# mega_pin_out.net
KiCad netlist of a schematic drawn in EAGLE
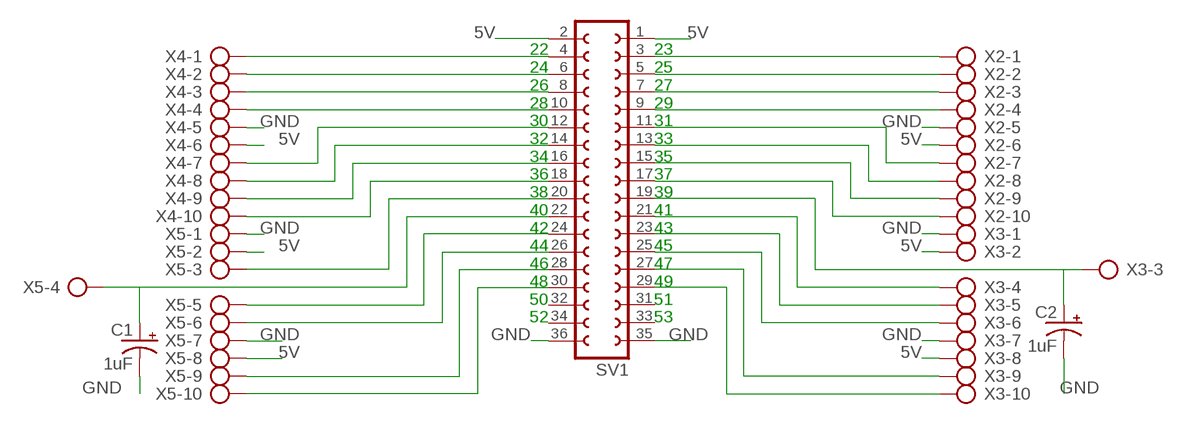
[diagram p0: schematic, sheet 1]

(export (version "E")
  (design (tool "Eeschema 10.0.6"))
  (components
    (comp (ref "C1")
      (value "1uF")
      (footprint "eagle-import:E2-4")
      (libsource (lib "eagle-import") (part "CPOL-USE2-4"))
    )
    (comp (ref "C2")
      (value "1uF")
      (footprint "eagle-import:E2-4")
      (libsource (lib "eagle-import") (part "CPOL-USE2-4"))
    )
    (comp (ref "SV1")
      (value "FE18-2")
      (footprint "eagle-import:FE18-2")
      (libsource (lib "eagle-import") (part "FE18-2"))
    )
    (comp (ref "X2")
      (value "AK500/10")
      (footprint "eagle-import:AK500_10")
      (libsource (lib "eagle-import") (part "AK500/10"))
    )
    (comp (ref "X3")
      (value "AK500/10")
      (footprint "eagle-import:AK500_10")
      (libsource (lib "eagle-import") (part "AK500/10"))
    )
    (comp (ref "X4")
      (value "AK500/10")
      (footprint "eagle-import:AK500_10")
      (libsource (lib "eagle-import") (part "AK500/10"))
    )
    (comp (ref "X5")
      (value "AK500/10")
      (footprint "eagle-import:AK500_10")
      (libsource (lib "eagle-import") (part "AK500/10"))
    )
  )
  (nets
    (net (code "1") (name "/5V") (class "Default")
      (node (ref "SV1") (pin "1") (pinfunction "1_1") (pintype "passive"))
      (node (ref "SV1") (pin "2") (pinfunction "2_2") (pintype "passive"))
      (node (ref "X2") (pin "6") (pinfunction "KL_6") (pintype "passive"))
      (node (ref "X3") (pin "2") (pinfunction "KL_2") (pintype "passive"))
      (node (ref "X3") (pin "8") (pinfunction "KL_8") (pintype "passive"))
      (node (ref "X4") (pin "6") (pinfunction "KL_6") (pintype "passive"))
      (node (ref "X5") (pin "2") (pinfunction "KL_2") (pintype "passive"))
      (node (ref "X5") (pin "8") (pinfunction "KL_8") (pintype "passive"))
    )
    (net (code "2") (name "/GND") (class "Default")
      (node (ref "C1") (pin "-") (pinfunction "-_-") (pintype "passive"))
      (node (ref "C2") (pin "-") (pinfunction "-_-") (pintype "passive"))
      (node (ref "SV1") (pin "35") (pinfunction "35_35") (pintype "passive"))
      (node (ref "SV1") (pin "36") (pinfunction "36_36") (pintype "passive"))
      (node (ref "X2") (pin "5") (pinfunction "KL_5") (pintype "passive"))
      (node (ref "X3") (pin "1") (pinfunction "KL_1") (pintype "passive"))
      (node (ref "X3") (pin "7") (pinfunction "KL_7") (pintype "passive"))
      (node (ref "X4") (pin "5") (pinfunction "KL_5") (pintype "passive"))
      (node (ref "X5") (pin "1") (pinfunction "KL_1") (pintype "passive"))
      (node (ref "X5") (pin "7") (pinfunction "KL_7") (pintype "passive"))
    )
    (net (code "3") (name "Net-(X2A-KL)") (class "Default")
      (node (ref "SV1") (pin "3") (pinfunction "3_3") (pintype "passive"))
      (node (ref "X2") (pin "1") (pinfunction "KL_1") (pintype "passive"))
    )
    (net (code "4") (name "Net-(X2B-KL)") (class "Default")
      (node (ref "SV1") (pin "17") (pinfunction "17_17") (pintype "passive"))
      (node (ref "X2") (pin "10") (pinfunction "KL_10") (pintype "passive"))
    )
    (net (code "5") (name "Net-(X2C-KL)") (class "Default")
      (node (ref "SV1") (pin "5") (pinfunction "5_5") (pintype "passive"))
      (node (ref "X2") (pin "2") (pinfunction "KL_2") (pintype "passive"))
    )
    (net (code "6") (name "Net-(X2D-KL)") (class "Default")
      (node (ref "SV1") (pin "7") (pinfunction "7_7") (pintype "passive"))
      (node (ref "X2") (pin "3") (pinfunction "KL_3") (pintype "passive"))
    )
    (net (code "7") (name "Net-(X2E-KL)") (class "Default")
      (node (ref "SV1") (pin "9") (pinfunction "9_9") (pintype "passive"))
      (node (ref "X2") (pin "4") (pinfunction "KL_4") (pintype "passive"))
    )
    (net (code "8") (name "Net-(X2H-KL)") (class "Default")
      (node (ref "SV1") (pin "11") (pinfunction "11_11") (pintype "passive"))
      (node (ref "X2") (pin "7") (pinfunction "KL_7") (pintype "passive"))
    )
    (net (code "9") (name "Net-(X2I-KL)") (class "Default")
      (node (ref "SV1") (pin "13") (pinfunction "13_13") (pintype "passive"))
      (node (ref "X2") (pin "8") (pinfunction "KL_8") (pintype "passive"))
    )
    (net (code "10") (name "Net-(X2J-KL)") (class "Default")
      (node (ref "SV1") (pin "15") (pinfunction "15_15") (pintype "passive"))
      (node (ref "X2") (pin "9") (pinfunction "KL_9") (pintype "passive"))
    )
    (net (code "11") (name "Net-(X3B-KL)") (class "Default")
      (node (ref "SV1") (pin "29") (pinfunction "29_29") (pintype "passive"))
      (node (ref "X3") (pin "10") (pinfunction "KL_10") (pintype "passive"))
    )
    (net (code "12") (name "Net-(X3D-KL)") (class "Default")
      (node (ref "C2") (pin "+") (pinfunction "+_+") (pintype "passive"))
      (node (ref "SV1") (pin "19") (pinfunction "19_19") (pintype "passive"))
      (node (ref "X3") (pin "3") (pinfunction "KL_3") (pintype "passive"))
    )
    (net (code "13") (name "Net-(X3E-KL)") (class "Default")
      (node (ref "SV1") (pin "21") (pinfunction "21_21") (pintype "passive"))
      (node (ref "X3") (pin "4") (pinfunction "KL_4") (pintype "passive"))
    )
    (net (code "14") (name "Net-(X3F-KL)") (class "Default")
      (node (ref "SV1") (pin "23") (pinfunction "23_23") (pintype "passive"))
      (node (ref "X3") (pin "5") (pinfunction "KL_5") (pintype "passive"))
    )
    (net (code "15") (name "Net-(X3G-KL)") (class "Default")
      (node (ref "SV1") (pin "25") (pinfunction "25_25") (pintype "passive"))
      (node (ref "X3") (pin "6") (pinfunction "KL_6") (pintype "passive"))
    )
    (net (code "16") (name "Net-(X3J-KL)") (class "Default")
      (node (ref "SV1") (pin "27") (pinfunction "27_27") (pintype "passive"))
      (node (ref "X3") (pin "9") (pinfunction "KL_9") (pintype "passive"))
    )
    (net (code "17") (name "Net-(X4A-KL)") (class "Default")
      (node (ref "SV1") (pin "4") (pinfunction "4_4") (pintype "passive"))
      (node (ref "X4") (pin "1") (pinfunction "KL_1") (pintype "passive"))
    )
    (net (code "18") (name "Net-(X4B-KL)") (class "Default")
      (node (ref "SV1") (pin "18") (pinfunction "18_18") (pintype "passive"))
      (node (ref "X4") (pin "10") (pinfunction "KL_10") (pintype "passive"))
    )
    (net (code "19") (name "Net-(X4C-KL)") (class "Default")
      (node (ref "SV1") (pin "6") (pinfunction "6_6") (pintype "passive"))
      (node (ref "X4") (pin "2") (pinfunction "KL_2") (pintype "passive"))
    )
    (net (code "20") (name "Net-(X4D-KL)") (class "Default")
      (node (ref "SV1") (pin "8") (pinfunction "8_8") (pintype "passive"))
      (node (ref "X4") (pin "3") (pinfunction "KL_3") (pintype "passive"))
    )
    (net (code "21") (name "Net-(X4E-KL)") (class "Default")
      (node (ref "SV1") (pin "10") (pinfunction "10_10") (pintype "passive"))
      (node (ref "X4") (pin "4") (pinfunction "KL_4") (pintype "passive"))
    )
    (net (code "22") (name "Net-(X4H-KL)") (class "Default")
      (node (ref "SV1") (pin "12") (pinfunction "12_12") (pintype "passive"))
      (node (ref "X4") (pin "7") (pinfunction "KL_7") (pintype "passive"))
    )
    (net (code "23") (name "Net-(X4I-KL)") (class "Default")
      (node (ref "SV1") (pin "14") (pinfunction "14_14") (pintype "passive"))
      (node (ref "X4") (pin "8") (pinfunction "KL_8") (pintype "passive"))
    )
    (net (code "24") (name "Net-(X4J-KL)") (class "Default")
      (node (ref "SV1") (pin "16") (pinfunction "16_16") (pintype "passive"))
      (node (ref "X4") (pin "9") (pinfunction "KL_9") (pintype "passive"))
    )
    (net (code "25") (name "Net-(X5B-KL)") (class "Default")
      (node (ref "SV1") (pin "30") (pinfunction "30_30") (pintype "passive"))
      (node (ref "X5") (pin "10") (pinfunction "KL_10") (pintype "passive"))
    )
    (net (code "26") (name "Net-(X5D-KL)") (class "Default")
      (node (ref "SV1") (pin "20") (pinfunction "20_20") (pintype "passive"))
      (node (ref "X5") (pin "3") (pinfunction "KL_3") (pintype "passive"))
    )
    (net (code "27") (name "Net-(X5E-KL)") (class "Default")
      (node (ref "C1") (pin "+") (pinfunction "+_+") (pintype "passive"))
      (node (ref "SV1") (pin "22") (pinfunction "22_22") (pintype "passive"))
      (node (ref "X5") (pin "4") (pinfunction "KL_4") (pintype "passive"))
    )
    (net (code "28") (name "Net-(X5F-KL)") (class "Default")
      (node (ref "SV1") (pin "24") (pinfunction "24_24") (pintype "passive"))
      (node (ref "X5") (pin "5") (pinfunction "KL_5") (pintype "passive"))
    )
    (net (code "29") (name "Net-(X5G-KL)") (class "Default")
      (node (ref "SV1") (pin "26") (pinfunction "26_26") (pintype "passive"))
      (node (ref "X5") (pin "6") (pinfunction "KL_6") (pintype "passive"))
    )
    (net (code "30") (name "Net-(X5J-KL)") (class "Default")
      (node (ref "SV1") (pin "28") (pinfunction "28_28") (pintype "passive"))
      (node (ref "X5") (pin "9") (pinfunction "KL_9") (pintype "passive"))
    )
    (net (code "31") (name "unconnected-(SV1-Pad31)") (class "Default")
      (node (ref "SV1") (pin "31") (pinfunction "31_31") (pintype "passive"))
    )
    (net (code "32") (name "unconnected-(SV1-Pad32)") (class "Default")
      (node (ref "SV1") (pin "32") (pinfunction "32_32") (pintype "passive"))
    )
    (net (code "33") (name "unconnected-(SV1-Pad33)") (class "Default")
      (node (ref "SV1") (pin "33") (pinfunction "33_33") (pintype "passive"))
    )
    (net (code "34") (name "unconnected-(SV1-Pad34)") (class "Default")
      (node (ref "SV1") (pin "34") (pinfunction "34_34") (pintype "passive"))
    )
  )
)
